# EXT_SMART.net
KiCad netlist of a schematic drawn in EAGLE
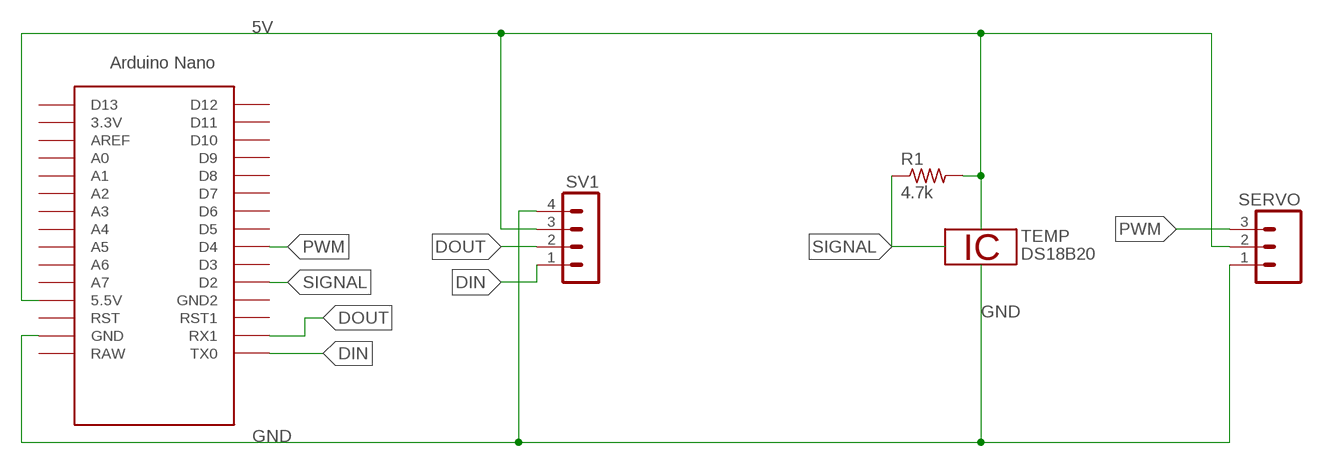
[diagram p0: schematic, sheet 1]

(export (version "E")
  (design (tool "Eeschema 10.0.6"))
  (components
    (comp (ref "R1")
      (value "4.7k")
      (footprint "eagle-import:0204_7")
      (libsource (lib "eagle-import") (part "R-US_0204/7"))
    )
    (comp (ref "SERVO")
      (value "M03")
      (footprint "eagle-import:03P")
      (libsource (lib "eagle-import") (part "M03"))
    )
    (comp (ref "SV1")
      (value "MA04-1")
      (footprint "eagle-import:MA04-1")
      (libsource (lib "eagle-import") (part "MA04-1"))
    )
    (comp (ref "TEMP")
      (value "DS18B20")
      (footprint "eagle-import:TO92-")
      (libsource (lib "eagle-import") (part "DS18B20"))
    )
    (comp (ref "U$1")
      (value "NANO")
      (footprint "eagle-import:NANO")
      (libsource (lib "eagle-import") (part "NANO"))
    )
  )
  (nets
    (net (code "1") (name "/5V") (class "Default")
      (node (ref "R1") (pin "2") (pinfunction "2_2") (pintype "passive"))
      (node (ref "SERVO") (pin "2") (pinfunction "2_2") (pintype "passive"))
      (node (ref "SV1") (pin "3") (pinfunction "3_3") (pintype "passive"))
      (node (ref "U$1") (pin "5V") (pinfunction "5.5V_5V") (pintype "bidirectional"))
    )
    (net (code "2") (name "/GND") (class "Default")
      (node (ref "SERVO") (pin "1") (pinfunction "1_1") (pintype "passive"))
      (node (ref "SV1") (pin "4") (pinfunction "4_4") (pintype "passive"))
      (node (ref "U$1") (pin "GND") (pinfunction "GND_GND") (pintype "bidirectional"))
    )
    (net (code "3") (name "DIN") (class "Default")
      (node (ref "SV1") (pin "1") (pinfunction "1_1") (pintype "passive"))
      (node (ref "U$1") (pin "TX0") (pinfunction "TX0_TX0") (pintype "bidirectional"))
    )
    (net (code "4") (name "DOUT") (class "Default")
      (node (ref "SV1") (pin "2") (pinfunction "2_2") (pintype "passive"))
      (node (ref "U$1") (pin "RX1") (pinfunction "RX1_RX1") (pintype "bidirectional"))
    )
    (net (code "5") (name "PWM") (class "Default")
      (node (ref "SERVO") (pin "3") (pinfunction "3_3") (pintype "passive"))
      (node (ref "U$1") (pin "D4") (pinfunction "D4_D4") (pintype "bidirectional"))
    )
    (net (code "6") (name "SIGNAL") (class "Default")
      (node (ref "R1") (pin "1") (pinfunction "1_1") (pintype "passive"))
      (node (ref "U$1") (pin "D2") (pinfunction "D2_D2") (pintype "bidirectional"))
    )
    (net (code "7") (name "unconnected-(U$1-GND2-PadGND1)") (class "Default")
      (node (ref "U$1") (pin "GND1") (pinfunction "GND2_GND1") (pintype "bidirectional"))
    )
    (net (code "8") (name "unconnected-(U$1-Pad3.3V)") (class "Default")
      (node (ref "U$1") (pin "3.3V") (pinfunction "3.3V_3.3V") (pintype "bidirectional"))
    )
    (net (code "9") (name "unconnected-(U$1-PadA0)") (class "Default")
      (node (ref "U$1") (pin "A0") (pinfunction "A0_A0") (pintype "bidirectional"))
    )
    (net (code "10") (name "unconnected-(U$1-PadA1)") (class "Default")
      (node (ref "U$1") (pin "A1") (pinfunction "A1_A1") (pintype "bidirectional"))
    )
    (net (code "11") (name "unconnected-(U$1-PadA2)") (class "Default")
      (node (ref "U$1") (pin "A2") (pinfunction "A2_A2") (pintype "bidirectional"))
    )
    (net (code "12") (name "unconnected-(U$1-PadA3)") (class "Default")
      (node (ref "U$1") (pin "A3") (pinfunction "A3_A3") (pintype "bidirectional"))
    )
    (net (code "13") (name "unconnected-(U$1-PadA4)") (class "Default")
      (node (ref "U$1") (pin "A4") (pinfunction "A4_A4") (pintype "bidirectional"))
    )
    (net (code "14") (name "unconnected-(U$1-PadA5)") (class "Default")
      (node (ref "U$1") (pin "A5") (pinfunction "A5_A5") (pintype "bidirectional"))
    )
    (net (code "15") (name "unconnected-(U$1-PadA6)") (class "Default")
      (node (ref "U$1") (pin "A6") (pinfunction "A6_A6") (pintype "bidirectional"))
    )
    (net (code "16") (name "unconnected-(U$1-PadA7)") (class "Default")
      (node (ref "U$1") (pin "A7") (pinfunction "A7_A7") (pintype "bidirectional"))
    )
    (net (code "17") (name "unconnected-(U$1-PadAREF)") (class "Default")
      (node (ref "U$1") (pin "AREF") (pinfunction "AREF_AREF") (pintype "bidirectional"))
    )
    (net (code "18") (name "unconnected-(U$1-PadD3)") (class "Default")
      (node (ref "U$1") (pin "D3") (pinfunction "D3_D3") (pintype "bidirectional"))
    )
    (net (code "19") (name "unconnected-(U$1-PadD5)") (class "Default")
      (node (ref "U$1") (pin "D5") (pinfunction "D5_D5") (pintype "bidirectional"))
    )
    (net (code "20") (name "unconnected-(U$1-PadD6)") (class "Default")
      (node (ref "U$1") (pin "D6") (pinfunction "D6_D6") (pintype "bidirectional"))
    )
    (net (code "21") (name "unconnected-(U$1-PadD7)") (class "Default")
      (node (ref "U$1") (pin "D7") (pinfunction "D7_D7") (pintype "bidirectional"))
    )
    (net (code "22") (name "unconnected-(U$1-PadD8)") (class "Default")
      (node (ref "U$1") (pin "D8") (pinfunction "D8_D8") (pintype "bidirectional"))
    )
    (net (code "23") (name "unconnected-(U$1-PadD9)") (class "Default")
      (node (ref "U$1") (pin "D9") (pinfunction "D9_D9") (pintype "bidirectional"))
    )
    (net (code "24") (name "unconnected-(U$1-PadD10)") (class "Default")
      (node (ref "U$1") (pin "D10") (pinfunction "D10_D10") (pintype "bidirectional"))
    )
    (net (code "25") (name "unconnected-(U$1-PadD11)") (class "Default")
      (node (ref "U$1") (pin "D11") (pinfunction "D11_D11") (pintype "bidirectional"))
    )
    (net (code "26") (name "unconnected-(U$1-PadD12)") (class "Default")
      (node (ref "U$1") (pin "D12") (pinfunction "D12_D12") (pintype "bidirectional"))
    )
    (net (code "27") (name "unconnected-(U$1-PadD13)") (class "Default")
      (node (ref "U$1") (pin "D13") (pinfunction "D13_D13") (pintype "bidirectional"))
    )
    (net (code "28") (name "unconnected-(U$1-PadICSP1)") (class "Default")
      (node (ref "U$1") (pin "ICSP1") (pinfunction "ICSP1_ICSP1") (pintype "bidirectional"))
    )
    (net (code "29") (name "unconnected-(U$1-PadICSP2)") (class "Default")
      (node (ref "U$1") (pin "ICSP2") (pinfunction "ICSP2_ICSP2") (pintype "bidirectional"))
    )
    (net (code "30") (name "unconnected-(U$1-PadICSP3)") (class "Default")
      (node (ref "U$1") (pin "ICSP3") (pinfunction "ICSP3_ICSP3") (pintype "bidirectional"))
    )
    (net (code "31") (name "unconnected-(U$1-PadICSP4)") (class "Default")
      (node (ref "U$1") (pin "ICSP4") (pinfunction "ICSP4_ICSP4") (pintype "bidirectional"))
    )
    (net (code "32") (name "unconnected-(U$1-PadICSP5)") (class "Default")
      (node (ref "U$1") (pin "ICSP5") (pinfunction "ICSP5_ICSP5") (pintype "bidirectional"))
    )
    (net (code "33") (name "unconnected-(U$1-PadICSP6)") (class "Default")
      (node (ref "U$1") (pin "ICSP6") (pinfunction "ICSP6_ICSP6") (pintype "bidirectional"))
    )
    (net (code "34") (name "unconnected-(U$1-PadRAW)") (class "Default")
      (node (ref "U$1") (pin "RAW") (pinfunction "RAW_RAW") (pintype "bidirectional"))
    )
    (net (code "35") (name "unconnected-(U$1-PadRST)") (class "Default")
      (node (ref "U$1") (pin "RST") (pinfunction "RST_RST") (pintype "bidirectional"))
    )
    (net (code "36") (name "unconnected-(U$1-PadRST1)") (class "Default")
      (node (ref "U$1") (pin "RST1") (pinfunction "RST1_RST1") (pintype "bidirectional"))
    )
  )
)
